# Reference_2V5.net
KiCad netlist of a schematic drawn in Altium Designer
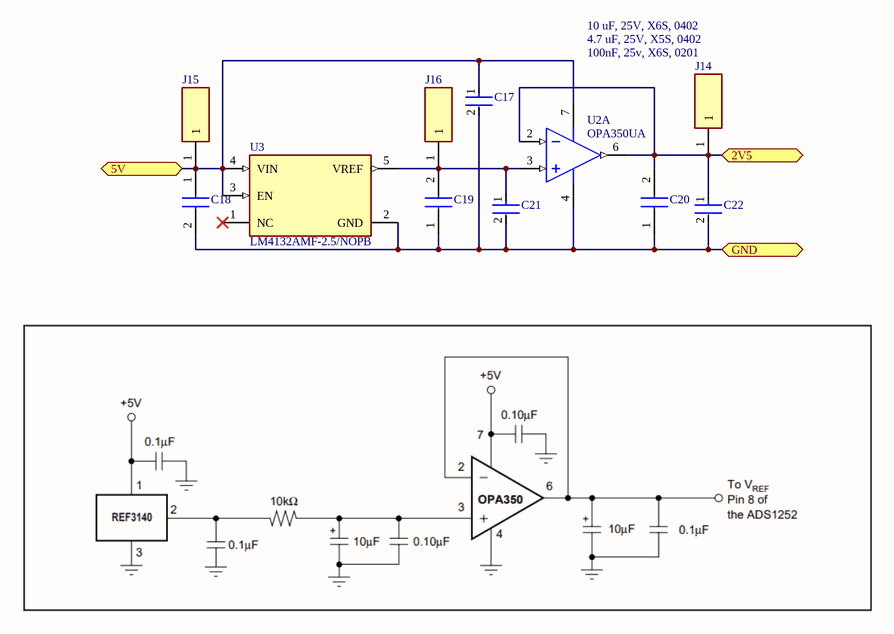
[diagram p0: Reference_2V5.SchDoc]

(export (version "E")
  (design (tool "Eeschema 10.0.6"))
  (components
    (comp (ref "C17")
      (value "100nF, 25v, X6S, 0201")
      (footprint "FP-GRM033-0_03-IPC_B")
      (description "Chip Multilayer Ceramic Capacitors for General Purpose, 0201, 0.10uF, X6S, 22%, 10%, 25V")
      (fields (field (name "TOLERANCE") "10%"))
      (libsource (lib "Altium Content Vault") (part "b4654b650e69147ec39a6b967a45e02"))
    )
    (comp (ref "C18")
      (value "10 uF, 25V, X6S, 0402")
      (footprint "SamacSys:CAPC1005X70N")
      (description "Capacitor")
      (fields
        (field (name "MANUFACTURER_PART_NUMBER") "GRM155F51E104ZA01E")
        (field (name "MOUSER PART NUMBER") "81-GRM15F51E104ZA01E")
      )
      (libsource (lib "*") (part "GRM155F51E104ZA01E"))
    )
    (comp (ref "C19")
      (value "4.7 uF, 25V, X5S, 0402")
      (footprint "SamacSys:GRM15x")
      (description "Capacitor")
      (fields
        (field (name "MANUFACTURER_PART_NUMBER") "GRM155C61E475ME15J")
        (field (name "MOUSER PART NUMBER") "81-GRM15C61E475ME15J")
      )
      (libsource (lib "*") (part "GRM155C61E475ME15J"))
    )
    (comp (ref "C20")
      (value "10 uF, 25V, X6S, 0402")
      (footprint "SamacSys:CAPC1005X70N")
      (description "Capacitor")
      (fields
        (field (name "MANUFACTURER_PART_NUMBER") "GRM155F51E104ZA01E")
        (field (name "MOUSER PART NUMBER") "81-GRM15F51E104ZA01E")
      )
      (libsource (lib "*") (part "GRM155F51E104ZA01E"))
    )
    (comp (ref "C21")
      (value "100nF, 25v, X6S, 0201")
      (footprint "FP-GRM033-0_03-IPC_B")
      (description "Chip Multilayer Ceramic Capacitors for General Purpose, 0201, 0.10uF, X6S, 22%, 10%, 25V")
      (fields (field (name "TOLERANCE") "10%"))
      (libsource (lib "Altium Content Vault") (part "b4654b650e69147ec39a6b967a45e02"))
    )
    (comp (ref "C22")
      (value "100nF, 25v, X6S, 0201")
      (footprint "FP-GRM033-0_03-IPC_B")
      (description "Chip Multilayer Ceramic Capacitors for General Purpose, 0201, 0.10uF, X6S, 22%, 10%, 25V")
      (fields (field (name "TOLERANCE") "10%"))
      (libsource (lib "Altium Content Vault") (part "b4654b650e69147ec39a6b967a45e02"))
    )
    (comp (ref "J14")
      (value "TestPad")
      (footprint "SamacSys:TestPad")
      (description "Connector")
      (fields
        (field (name "MANUFACTURER_PART_NUMBER") "61300111121")
        (field (name "MOUSER PART NUMBER") "710-61300111121")
      )
      (libsource (lib "") (part "61300111121_1"))
    )
    (comp (ref "J15")
      (value "TestPad")
      (footprint "SamacSys:TestPad")
      (description "Connector")
      (fields
        (field (name "MANUFACTURER_PART_NUMBER") "61300111121")
        (field (name "MOUSER PART NUMBER") "710-61300111121")
      )
      (libsource (lib "*") (part "61300111121"))
    )
    (comp (ref "J16")
      (value "TestPad")
      (footprint "SamacSys:TestPad")
      (description "Connector")
      (fields
        (field (name "MANUFACTURER_PART_NUMBER") "61300111121")
        (field (name "MOUSER PART NUMBER") "710-61300111121")
      )
      (libsource (lib "*") (part "61300111121"))
    )
    (comp (ref "U2")
      (value "OPA350UA")
      (footprint "D0008A_M")
      (fields (field (name "MANUFACTURER") "Texas Instruments"))
      (libsource (lib "Altium Content Vault") (part "TI-OPA-8_1"))
    )
    (comp (ref "U3")
      (value "LM4132AMF-2.5/NOPB")
      (footprint "FP-DBV0005A-IPC_C")
      (description "IC VREF SERIES 0.05% SOT23-5")
      (fields (field (name "TOLERANCE") "0.05%"))
      (libsource (lib "Altium Content Vault") (part "83a8c20666b8818ecf60699c622df6d"))
    )
  )
  (nets
    (net (code "1") (name "/2V5") (class "Default")
      (node (ref "C20") (pin "2") (pinfunction "2_2") (pintype "passive"))
      (node (ref "C22") (pin "1") (pinfunction "1_1") (pintype "passive"))
      (node (ref "J14") (pin "1") (pinfunction "1_1") (pintype "passive"))
      (node (ref "U2") (pin "2") (pinfunction "IN-_2") (pintype "input"))
      (node (ref "U2") (pin "6") (pinfunction "OUT_6") (pintype "output"))
    )
    (net (code "2") (name "/5V") (class "Default")
      (node (ref "C17") (pin "1") (pinfunction "1_1") (pintype "passive"))
      (node (ref "C18") (pin "1") (pinfunction "1_1") (pintype "passive"))
      (node (ref "J15") (pin "1") (pinfunction "1_1") (pintype "passive"))
      (node (ref "U2") (pin "7") (pinfunction "V+_7") (pintype "power_in"))
      (node (ref "U3") (pin "3") (pinfunction "EN_3") (pintype "input"))
      (node (ref "U3") (pin "4") (pinfunction "VIN_4") (pintype "input"))
    )
    (net (code "3") (name "/GND") (class "Default")
      (node (ref "C17") (pin "2") (pinfunction "2_2") (pintype "passive"))
      (node (ref "C18") (pin "2") (pinfunction "2_2") (pintype "passive"))
      (node (ref "C19") (pin "1") (pinfunction "1_1") (pintype "passive"))
      (node (ref "C20") (pin "1") (pinfunction "1_1") (pintype "passive"))
      (node (ref "C21") (pin "2") (pinfunction "2_2") (pintype "passive"))
      (node (ref "C22") (pin "2") (pinfunction "2_2") (pintype "passive"))
      (node (ref "U2") (pin "4") (pinfunction "V-_4") (pintype "power_in"))
      (node (ref "U3") (pin "2") (pinfunction "GND_2") (pintype "power_in"))
    )
    (net (code "4") (name "Net-(U2A-IN+)") (class "Default")
      (node (ref "C19") (pin "2") (pinfunction "2_2") (pintype "passive"))
      (node (ref "C21") (pin "1") (pinfunction "1_1") (pintype "passive"))
      (node (ref "J16") (pin "1") (pinfunction "1_1") (pintype "passive"))
      (node (ref "U2") (pin "3") (pinfunction "IN+_3") (pintype "input"))
      (node (ref "U3") (pin "5") (pinfunction "VREF_5") (pintype "output"))
    )
    (net (code "5") (name "unconnected-(U3-NC-Pad1)") (class "Default")
      (node (ref "U3") (pin "1") (pinfunction "NC_1") (pintype "passive+no_connect"))
    )
  )
)
